# schematic.net
KiCad netlist of a schematic drawn in EasyEDA Pro
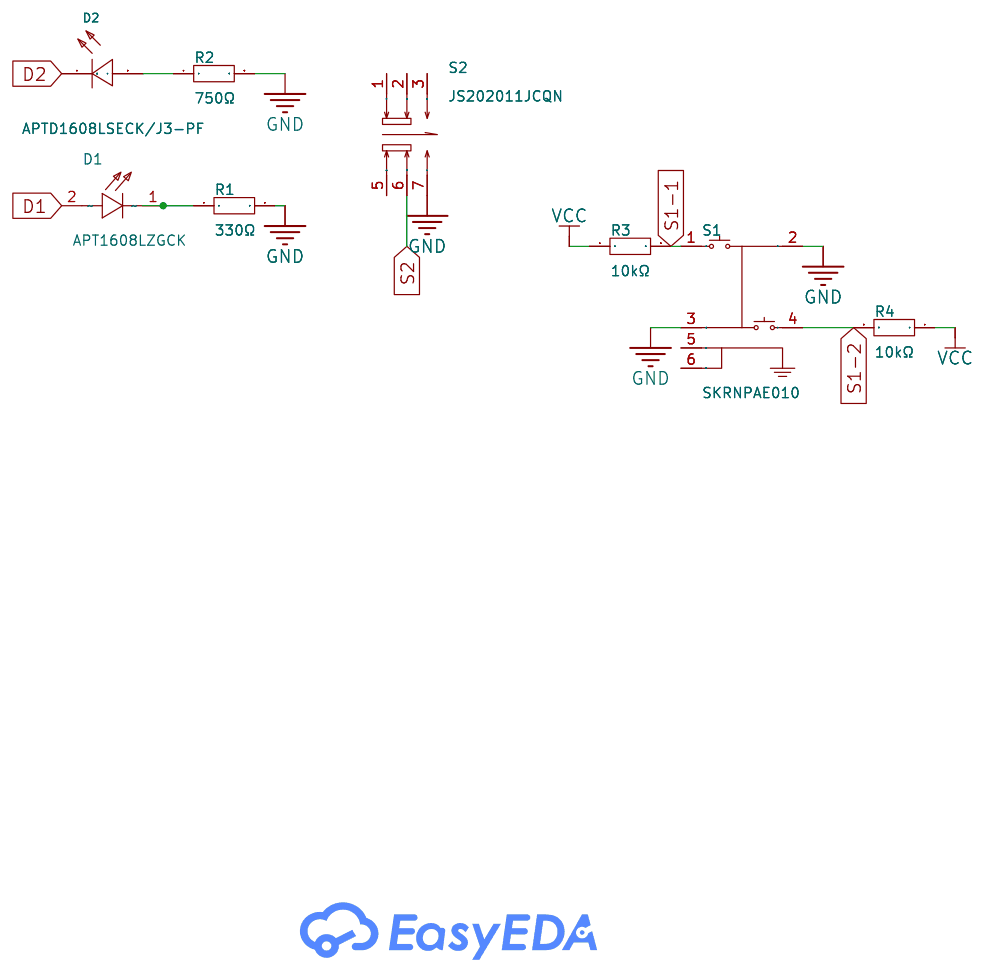
[diagram p0: schematic sheet]

(export (version "E")
  (design (tool "Eeschema 10.0.6"))
  (components
    (comp (ref "D1") (value "APT1608LZGCK") (libsource (lib "easyedapro") (part "APT1608LZGCK")))
    (comp (ref "D2")
      (value "APTD1608LSECK/J3-PF")
      (footprint "easyedapro:LED-SMD_L1.6-W0.8-RD")
      (fields (field (name "Manufacturer") "Kingbright"))
      (libsource (lib "easyedapro") (part "APTD1608LSECK/J3-PF"))
    )
    (comp (ref "R1")
      (value "330Ω")
      (footprint "easyedapro:R0603")
      (fields (field (name "Manufacturer Part") "RC0603JR-07330RL") (field (name "Manufacturer") "YAGEO(国巨)"))
      (libsource (lib "easyedapro") (part "RC0603JR-07330RL"))
    )
    (comp (ref "R2")
      (value "750Ω")
      (footprint "easyedapro:R0603")
      (fields (field (name "Manufacturer Part") "RC0603JR-07750RL") (field (name "Manufacturer") "YAGEO(国巨)"))
      (libsource (lib "easyedapro") (part "RC0603JR-07750RL"))
    )
    (comp (ref "R3")
      (value "10kΩ")
      (footprint "easyedapro:R0603")
      (fields (field (name "Manufacturer Part") "RC0603FR-0710KL") (field (name "Manufacturer") "YAGEO(国巨)"))
      (libsource (lib "easyedapro") (part "RC0603FR-0710KL"))
    )
    (comp (ref "R4")
      (value "10kΩ")
      (footprint "easyedapro:R0603")
      (fields (field (name "Manufacturer Part") "RC0603FR-0710KL") (field (name "Manufacturer") "YAGEO(国巨)"))
      (libsource (lib "easyedapro") (part "RC0603FR-0710KL"))
    )
    (comp (ref "S1")
      (value "SKRNPAE010")
      (footprint "easyedapro:SW-SMD_6P-L6.0-W6.0-P4.50-LS6.4")
      (fields (field (name "Manufacturer") "ALPSALPINE(阿尔卑斯阿尔派)"))
      (libsource (lib "easyedapro") (part "SKRNPAE010"))
    )
    (comp (ref "S2")
      (value "JS202011JCQN")
      (footprint "easyedapro:SW-SMD_JS202011JCQN")
      (fields (field (name "Manufacturer") "C&K"))
      (libsource (lib "easyedapro") (part "JS202011JCQN"))
    )
  )
  (nets
    (net (code "1") (name "D1") (class "Default")
      (node (ref "D1") (pin "2") (pinfunction "~_2") (pintype "unspecified"))
    )
    (net (code "2") (name "D2") (class "Default")
      (node (ref "D2") (pin "1") (pinfunction "C_1") (pintype "input"))
    )
    (net (code "3") (name "GND") (class "Default")
      (node (ref "R1") (pin "2") (pinfunction "2_2") (pintype "input"))
      (node (ref "R2") (pin "2") (pinfunction "2_2") (pintype "input"))
      (node (ref "S1") (pin "2") (pinfunction "2_2") (pintype "unspecified"))
      (node (ref "S1") (pin "3") (pinfunction "3_3") (pintype "unspecified"))
      (node (ref "S2") (pin "7") (pinfunction "7_7") (pintype "input"))
    )
    (net (code "4") (name "Net-(D1-~-Pad1)") (class "Default")
      (node (ref "D1") (pin "1") (pinfunction "~_1") (pintype "unspecified"))
      (node (ref "R1") (pin "1") (pinfunction "1_1") (pintype "input"))
    )
    (net (code "5") (name "Net-(D2-A)") (class "Default")
      (node (ref "D2") (pin "2") (pinfunction "A_2") (pintype "input"))
      (node (ref "R2") (pin "1") (pinfunction "1_1") (pintype "input"))
    )
    (net (code "6") (name "S1-1") (class "Default")
      (node (ref "R3") (pin "2") (pinfunction "2_2") (pintype "input"))
      (node (ref "S1") (pin "1") (pinfunction "1_1") (pintype "unspecified"))
    )
    (net (code "7") (name "S1-2") (class "Default")
      (node (ref "R4") (pin "2") (pinfunction "2_2") (pintype "input"))
      (node (ref "S1") (pin "4") (pinfunction "4_4") (pintype "unspecified"))
    )
    (net (code "8") (name "S2") (class "Default")
      (node (ref "S2") (pin "6") (pinfunction "6_6") (pintype "input"))
    )
    (net (code "9") (name "VCC") (class "Default")
      (node (ref "R3") (pin "1") (pinfunction "1_1") (pintype "input"))
      (node (ref "R4") (pin "1") (pinfunction "1_1") (pintype "input"))
    )
    (net (code "10") (name "unconnected-(S1-Pad5)") (class "Default")
      (node (ref "S1") (pin "5") (pinfunction "5_5") (pintype "unspecified"))
    )
    (net (code "11") (name "unconnected-(S1-Pad6)") (class "Default")
      (node (ref "S1") (pin "6") (pinfunction "6_6") (pintype "unspecified"))
    )
    (net (code "12") (name "unconnected-(S2-Pad1)") (class "Default")
      (node (ref "S2") (pin "1") (pinfunction "1_1") (pintype "input"))
    )
    (net (code "13") (name "unconnected-(S2-Pad2)") (class "Default")
      (node (ref "S2") (pin "2") (pinfunction "2_2") (pintype "input"))
    )
    (net (code "14") (name "unconnected-(S2-Pad3)") (class "Default")
      (node (ref "S2") (pin "3") (pinfunction "3_3") (pintype "input"))
    )
    (net (code "15") (name "unconnected-(S2-Pad5)") (class "Default")
      (node (ref "S2") (pin "5") (pinfunction "5_5") (pintype "input"))
    )
  )
)
